# Organ_fix1.net
KiCad netlist of a schematic drawn in EAGLE
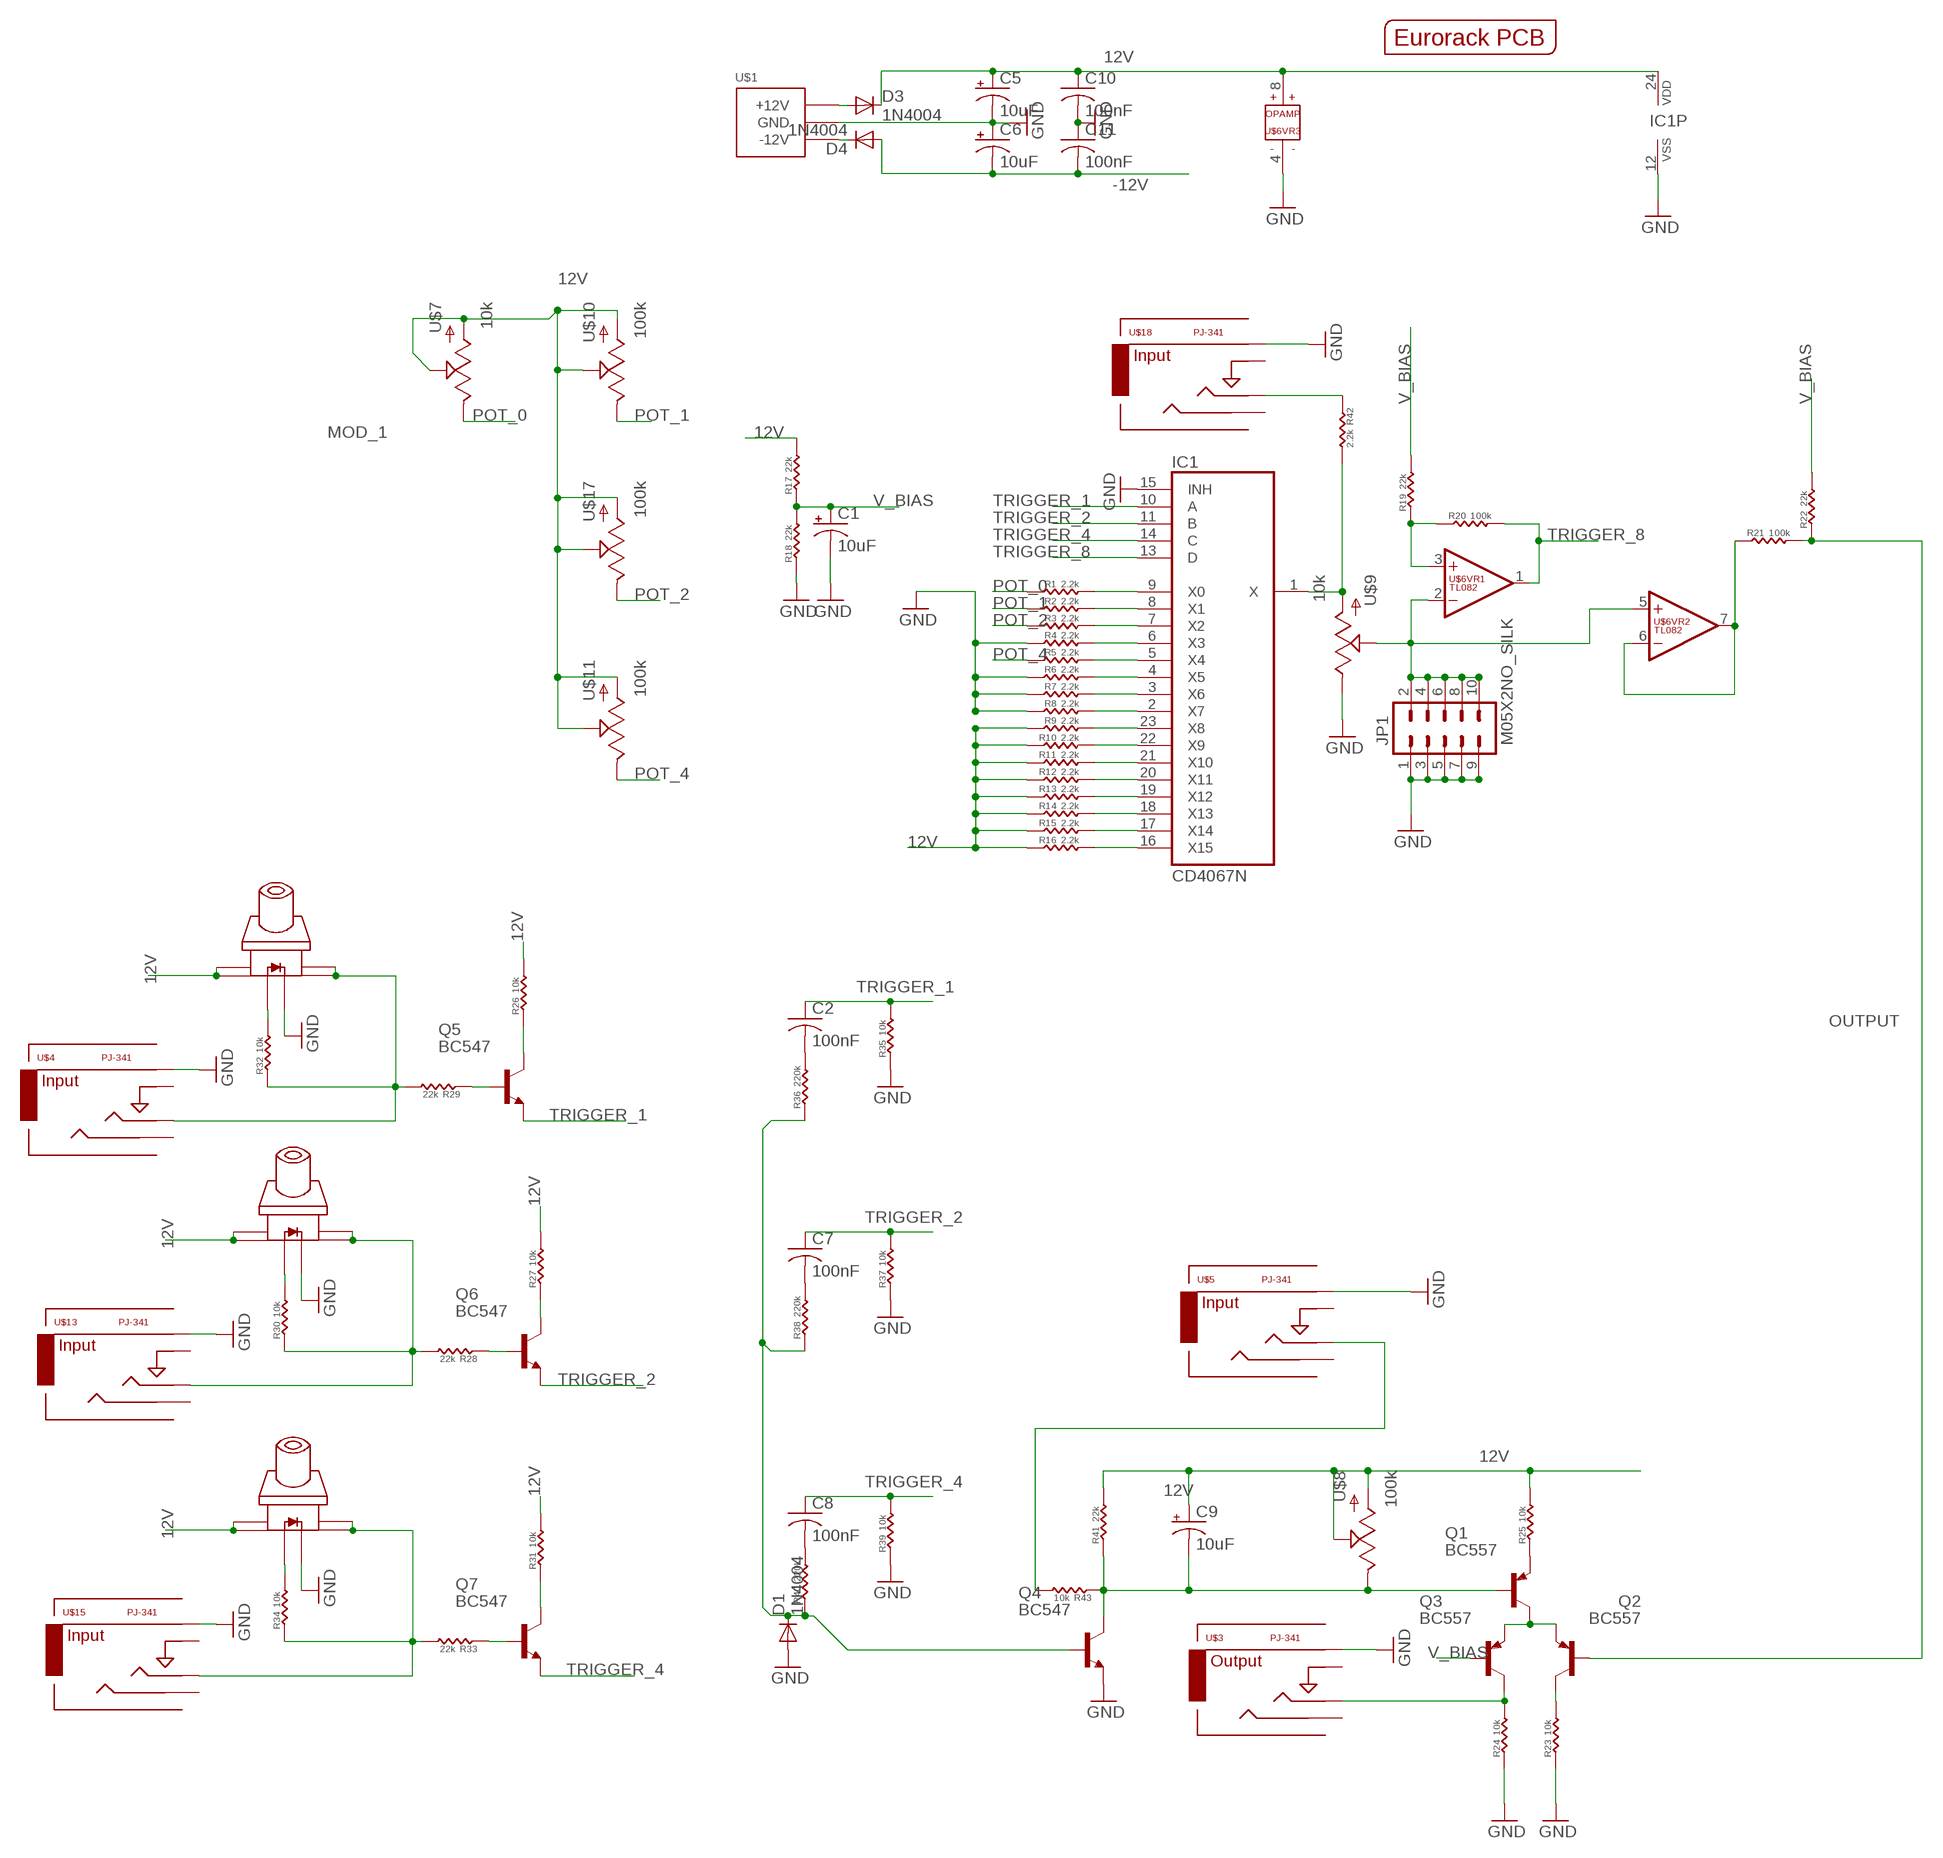
[diagram p0: schematic, sheet 1]

(export (version "E")
  (design (tool "Eeschema 10.0.6"))
  (components
    (comp (ref "C1")
      (value "10uF")
      (footprint "eagle-import:TT2D6")
      (libsource (lib "eagle-import") (part "CPOL-USTT2D6"))
    )
    (comp (ref "C2")
      (value "100nF")
      (footprint "eagle-import:C050-025X075")
      (libsource (lib "eagle-import") (part "C-US050-025X075"))
    )
    (comp (ref "C5")
      (value "10uF")
      (footprint "eagle-import:TT2D6")
      (libsource (lib "eagle-import") (part "CPOL-USTT2D6"))
    )
    (comp (ref "C6")
      (value "10uF")
      (footprint "eagle-import:TT2D6")
      (libsource (lib "eagle-import") (part "CPOL-USTT2D6"))
    )
    (comp (ref "C7")
      (value "100nF")
      (footprint "eagle-import:C050-025X075")
      (libsource (lib "eagle-import") (part "C-US050-025X075"))
    )
    (comp (ref "C8")
      (value "100nF")
      (footprint "eagle-import:C050-025X075")
      (libsource (lib "eagle-import") (part "C-US050-025X075"))
    )
    (comp (ref "C9")
      (value "10uF")
      (footprint "eagle-import:TT2D6")
      (libsource (lib "eagle-import") (part "CPOL-USTT2D6"))
    )
    (comp (ref "C10")
      (value "100nF")
      (footprint "eagle-import:C050-025X075")
      (libsource (lib "eagle-import") (part "C-US050-025X075"))
    )
    (comp (ref "C11")
      (value "100nF")
      (footprint "eagle-import:C050-025X075")
      (libsource (lib "eagle-import") (part "C-US050-025X075"))
    )
    (comp (ref "D1")
      (value "1N4004")
      (footprint "eagle-import:DO41-10")
      (libsource (lib "eagle-import") (part "1N4004"))
    )
    (comp (ref "D3")
      (value "1N4004")
      (footprint "eagle-import:DO41-10")
      (libsource (lib "eagle-import") (part "1N4004"))
    )
    (comp (ref "D4")
      (value "1N4004")
      (footprint "eagle-import:DO41-10")
      (libsource (lib "eagle-import") (part "1N4004"))
    )
    (comp (ref "IC1")
      (value "CD4067N")
      (footprint "eagle-import:DIL24-6")
      (libsource (lib "eagle-import") (part "4067N"))
    )
    (comp (ref "JP1")
      (value "M05X2NO_SILK")
      (footprint "eagle-import:2X5_NOSILK")
      (libsource (lib "eagle-import") (part "M05X2NO_SILK"))
    )
    (comp (ref "Q1")
      (value "BC557")
      (footprint "eagle-import:TO92")
      (libsource (lib "eagle-import") (part "BC557TO92"))
    )
    (comp (ref "Q2")
      (value "BC557")
      (footprint "eagle-import:TO92")
      (libsource (lib "eagle-import") (part "BC557TO92"))
    )
    (comp (ref "Q3")
      (value "BC557")
      (footprint "eagle-import:TO92")
      (libsource (lib "eagle-import") (part "BC557TO92"))
    )
    (comp (ref "Q4")
      (value "BC547")
      (footprint "eagle-import:TO92")
      (libsource (lib "eagle-import") (part "BC547"))
    )
    (comp (ref "Q5")
      (value "BC547")
      (footprint "eagle-import:TO92")
      (libsource (lib "eagle-import") (part "BC547"))
    )
    (comp (ref "Q6")
      (value "BC547")
      (footprint "eagle-import:TO92")
      (libsource (lib "eagle-import") (part "BC547"))
    )
    (comp (ref "Q7")
      (value "BC547")
      (footprint "eagle-import:TO92")
      (libsource (lib "eagle-import") (part "BC547"))
    )
    (comp (ref "R1")
      (value "2.2k")
      (footprint "eagle-import:0204_5")
      (libsource (lib "eagle-import") (part "R-US_0204/5"))
    )
    (comp (ref "R2")
      (value "2.2k")
      (footprint "eagle-import:0204_5")
      (libsource (lib "eagle-import") (part "R-US_0204/5"))
    )
    (comp (ref "R3")
      (value "2.2k")
      (footprint "eagle-import:0204_5")
      (libsource (lib "eagle-import") (part "R-US_0204/5"))
    )
    (comp (ref "R4")
      (value "2.2k")
      (footprint "eagle-import:0204_5")
      (libsource (lib "eagle-import") (part "R-US_0204/5"))
    )
    (comp (ref "R5")
      (value "2.2k")
      (footprint "eagle-import:0204_5")
      (libsource (lib "eagle-import") (part "R-US_0204/5"))
    )
    (comp (ref "R6")
      (value "2.2k")
      (footprint "eagle-import:0204_5")
      (libsource (lib "eagle-import") (part "R-US_0204/5"))
    )
    (comp (ref "R7")
      (value "2.2k")
      (footprint "eagle-import:0204_5")
      (libsource (lib "eagle-import") (part "R-US_0204/5"))
    )
    (comp (ref "R8")
      (value "2.2k")
      (footprint "eagle-import:0204_5")
      (libsource (lib "eagle-import") (part "R-US_0204/5"))
    )
    (comp (ref "R9")
      (value "2.2k")
      (footprint "eagle-import:0204_5")
      (libsource (lib "eagle-import") (part "R-US_0204/5"))
    )
    (comp (ref "R10")
      (value "2.2k")
      (footprint "eagle-import:0204_5")
      (libsource (lib "eagle-import") (part "R-US_0204/5"))
    )
    (comp (ref "R11")
      (value "2.2k")
      (footprint "eagle-import:0204_5")
      (libsource (lib "eagle-import") (part "R-US_0204/5"))
    )
    (comp (ref "R12")
      (value "2.2k")
      (footprint "eagle-import:0204_5")
      (libsource (lib "eagle-import") (part "R-US_0204/5"))
    )
    (comp (ref "R13")
      (value "2.2k")
      (footprint "eagle-import:0204_5")
      (libsource (lib "eagle-import") (part "R-US_0204/5"))
    )
    (comp (ref "R14")
      (value "2.2k")
      (footprint "eagle-import:0204_5")
      (libsource (lib "eagle-import") (part "R-US_0204/5"))
    )
    (comp (ref "R15")
      (value "2.2k")
      (footprint "eagle-import:0204_5")
      (libsource (lib "eagle-import") (part "R-US_0204/5"))
    )
    (comp (ref "R16")
      (value "2.2k")
      (footprint "eagle-import:0204_5")
      (libsource (lib "eagle-import") (part "R-US_0204/5"))
    )
    (comp (ref "R17")
      (value "22k")
      (footprint "eagle-import:0204_5")
      (libsource (lib "eagle-import") (part "R-US_0204/5"))
    )
    (comp (ref "R18")
      (value "22k")
      (footprint "eagle-import:0204_5")
      (libsource (lib "eagle-import") (part "R-US_0204/5"))
    )
    (comp (ref "R19")
      (value "22k")
      (footprint "eagle-import:0204_5")
      (libsource (lib "eagle-import") (part "R-US_0204/5"))
    )
    (comp (ref "R20")
      (value "100k")
      (footprint "eagle-import:0204_5")
      (libsource (lib "eagle-import") (part "R-US_0204/5"))
    )
    (comp (ref "R21")
      (value "100k")
      (footprint "eagle-import:0204_5")
      (libsource (lib "eagle-import") (part "R-US_0204/5"))
    )
    (comp (ref "R22")
      (value "22k")
      (footprint "eagle-import:0204_5")
      (libsource (lib "eagle-import") (part "R-US_0204/5"))
    )
    (comp (ref "R23")
      (value "10k")
      (footprint "eagle-import:0204_5")
      (libsource (lib "eagle-import") (part "R-US_0204/5"))
    )
    (comp (ref "R24")
      (value "10k")
      (footprint "eagle-import:0204_5")
      (libsource (lib "eagle-import") (part "R-US_0204/5"))
    )
    (comp (ref "R25")
      (value "10k")
      (footprint "eagle-import:0204_5")
      (libsource (lib "eagle-import") (part "R-US_0204/5"))
    )
    (comp (ref "R26")
      (value "10k")
      (footprint "eagle-import:0204_5")
      (libsource (lib "eagle-import") (part "R-US_0204/5"))
    )
    (comp (ref "R27")
      (value "10k")
      (footprint "eagle-import:0204_5")
      (libsource (lib "eagle-import") (part "R-US_0204/5"))
    )
    (comp (ref "R28")
      (value "22k")
      (footprint "eagle-import:0204_5")
      (libsource (lib "eagle-import") (part "R-US_0204/5"))
    )
    (comp (ref "R29")
      (value "22k")
      (footprint "eagle-import:0204_5")
      (libsource (lib "eagle-import") (part "R-US_0204/5"))
    )
    (comp (ref "R30")
      (value "10k")
      (footprint "eagle-import:0204_5")
      (libsource (lib "eagle-import") (part "R-US_0204/5"))
    )
    (comp (ref "R31")
      (value "10k")
      (footprint "eagle-import:0204_5")
      (libsource (lib "eagle-import") (part "R-US_0204/5"))
    )
    (comp (ref "R32")
      (value "10k")
      (footprint "eagle-import:0204_5")
      (libsource (lib "eagle-import") (part "R-US_0204/5"))
    )
    (comp (ref "R33")
      (value "22k")
      (footprint "eagle-import:0204_5")
      (libsource (lib "eagle-import") (part "R-US_0204/5"))
    )
    (comp (ref "R34")
      (value "10k")
      (footprint "eagle-import:0204_5")
      (libsource (lib "eagle-import") (part "R-US_0204/5"))
    )
    (comp (ref "R35")
      (value "10k")
      (footprint "eagle-import:0204_5")
      (libsource (lib "eagle-import") (part "R-US_0204/5"))
    )
    (comp (ref "R36")
      (value "220k")
      (footprint "eagle-import:0204_5")
      (libsource (lib "eagle-import") (part "R-US_0204/5"))
    )
    (comp (ref "R37")
      (value "10k")
      (footprint "eagle-import:0204_5")
      (libsource (lib "eagle-import") (part "R-US_0204/5"))
    )
    (comp (ref "R38")
      (value "220k")
      (footprint "eagle-import:0204_5")
      (libsource (lib "eagle-import") (part "R-US_0204/5"))
    )
    (comp (ref "R39")
      (value "10k")
      (footprint "eagle-import:0204_5")
      (libsource (lib "eagle-import") (part "R-US_0204/5"))
    )
    (comp (ref "R40")
      (value "220k")
      (footprint "eagle-import:0204_5")
      (libsource (lib "eagle-import") (part "R-US_0204/5"))
    )
    (comp (ref "R41")
      (value "22k")
      (footprint "eagle-import:0204_5")
      (libsource (lib "eagle-import") (part "R-US_0204/5"))
    )
    (comp (ref "R42")
      (value "2.2k")
      (footprint "eagle-import:0204_5")
      (libsource (lib "eagle-import") (part "R-US_0204/5"))
    )
    (comp (ref "R43")
      (value "10k")
      (footprint "eagle-import:0204_5")
      (libsource (lib "eagle-import") (part "R-US_0204/5"))
    )
    (comp (ref "U$1")
      (value "POWER_SIMPLE10")
      (footprint "eagle-import:POWER_10")
      (libsource (lib "eagle-import") (part "POWER_SIMPLE10"))
    )
    (comp (ref "U$2")
      (value "EURORACK_PCB12HP")
      (footprint "eagle-import:EURORACK12HPPCB")
      (libsource (lib "eagle-import") (part "EURORACK_PCB12HP"))
    )
    (comp (ref "U$3")
      (value "PJ-341")
      (footprint "eagle-import:3.5MM-JACK-SWITCH-13MM-OUTPUT")
      (libsource (lib "eagle-import") (part "AUDIO-JACKOUTPUT"))
    )
    (comp (ref "U$4")
      (value "PJ-341")
      (footprint "eagle-import:3.5MM-JACK-SWITCH-13MM-INPUT")
      (libsource (lib "eagle-import") (part "AUDIO-JACKINPUT"))
    )
    (comp (ref "U$5")
      (value "PJ-341")
      (footprint "eagle-import:3.5MM-JACK-SWITCH-13MM-INPUT")
      (libsource (lib "eagle-import") (part "AUDIO-JACKINPUT"))
    )
    (comp (ref "U$6")
      (value "TL082")
      (footprint "eagle-import:DIL08")
      (libsource (lib "eagle-import") (part "TL072DIP"))
    )
    (comp (ref "U$7")
      (value "10k")
      (footprint "eagle-import:POT_SMALLERHOLE")
      (libsource (lib "eagle-import") (part "POTZEPHPOT_SMALLHOLE"))
    )
    (comp (ref "U$8")
      (value "100k")
      (footprint "eagle-import:POT_SMALLERHOLE")
      (libsource (lib "eagle-import") (part "POTZEPHPOT_SMALLHOLE"))
    )
    (comp (ref "U$9")
      (value "10k")
      (footprint "eagle-import:POT_SMALLERHOLE")
      (libsource (lib "eagle-import") (part "POTZEPHPOT_SMALLHOLE"))
    )
    (comp (ref "U$10")
      (value "100k")
      (footprint "eagle-import:POT_SMALLERHOLE")
      (libsource (lib "eagle-import") (part "POTZEPHPOT_SMALLHOLE"))
    )
    (comp (ref "U$11")
      (value "100k")
      (footprint "eagle-import:POT_SMALLERHOLE")
      (libsource (lib "eagle-import") (part "POTZEPHPOT_SMALLHOLE"))
    )
    (comp (ref "U$12")
      (value "SWITCH_W_LED_PB6149L-X-102YELLOW")
      (footprint "eagle-import:PB6149L")
      (libsource (lib "eagle-import") (part "SWITCH_W_LED_PB6149L-X-102YELLOW"))
    )
    (comp (ref "U$13")
      (value "PJ-341")
      (footprint "eagle-import:3.5MM-JACK-SWITCH-13MM-INPUT")
      (libsource (lib "eagle-import") (part "AUDIO-JACKINPUT"))
    )
    (comp (ref "U$14")
      (value "SWITCH_W_LED_PB6149L-X-102YELLOW")
      (footprint "eagle-import:PB6149L")
      (libsource (lib "eagle-import") (part "SWITCH_W_LED_PB6149L-X-102YELLOW"))
    )
    (comp (ref "U$15")
      (value "PJ-341")
      (footprint "eagle-import:3.5MM-JACK-SWITCH-13MM-INPUT")
      (libsource (lib "eagle-import") (part "AUDIO-JACKINPUT"))
    )
    (comp (ref "U$16")
      (value "SWITCH_W_LED_PB6149L-X-102YELLOW")
      (footprint "eagle-import:PB6149L")
      (libsource (lib "eagle-import") (part "SWITCH_W_LED_PB6149L-X-102YELLOW"))
    )
    (comp (ref "U$17")
      (value "100k")
      (footprint "eagle-import:POT_SMALLERHOLE")
      (libsource (lib "eagle-import") (part "POTZEPHPOT_SMALLHOLE"))
    )
    (comp (ref "U$18")
      (value "PJ-341")
      (footprint "eagle-import:3.5MM-JACK-SWITCH-13MM-INPUT")
      (libsource (lib "eagle-import") (part "AUDIO-JACKINPUT"))
    )
  )
  (nets
    (net (code "1") (name "/-12V") (class "Default")
      (node (ref "C11") (pin "2") (pinfunction "2_2") (pintype "passive"))
      (node (ref "C6") (pin "-") (pinfunction "-_-") (pintype "passive"))
      (node (ref "D4") (pin "A") (pinfunction "A_A") (pintype "passive"))
    )
    (net (code "2") (name "/12V") (class "Default")
      (node (ref "C10") (pin "1") (pinfunction "1_1") (pintype "passive"))
      (node (ref "C5") (pin "+") (pinfunction "+_+") (pintype "passive"))
      (node (ref "C9") (pin "+") (pinfunction "+_+") (pintype "passive"))
      (node (ref "D3") (pin "C") (pinfunction "C_C") (pintype "passive"))
      (node (ref "IC1") (pin "24") (pinfunction "VDD_24") (pintype "power_in"))
      (node (ref "R10") (pin "1") (pinfunction "1_1") (pintype "passive"))
      (node (ref "R11") (pin "1") (pinfunction "1_1") (pintype "passive"))
      (node (ref "R12") (pin "1") (pinfunction "1_1") (pintype "passive"))
      (node (ref "R13") (pin "1") (pinfunction "1_1") (pintype "passive"))
      (node (ref "R14") (pin "1") (pinfunction "1_1") (pintype "passive"))
      (node (ref "R15") (pin "1") (pinfunction "1_1") (pintype "passive"))
      (node (ref "R16") (pin "1") (pinfunction "1_1") (pintype "passive"))
      (node (ref "R17") (pin "2") (pinfunction "2_2") (pintype "passive"))
      (node (ref "R25") (pin "2") (pinfunction "2_2") (pintype "passive"))
      (node (ref "R26") (pin "2") (pinfunction "2_2") (pintype "passive"))
      (node (ref "R27") (pin "2") (pinfunction "2_2") (pintype "passive"))
      (node (ref "R31") (pin "2") (pinfunction "2_2") (pintype "passive"))
      (node (ref "R41") (pin "2") (pinfunction "2_2") (pintype "passive"))
      (node (ref "R9") (pin "1") (pinfunction "1_1") (pintype "passive"))
      (node (ref "U$10") (pin "P$2") (pinfunction "S_P$2") (pintype "passive"))
      (node (ref "U$10") (pin "P$3") (pinfunction "A_P$3") (pintype "passive"))
      (node (ref "U$11") (pin "P$2") (pinfunction "S_P$2") (pintype "passive"))
      (node (ref "U$11") (pin "P$3") (pinfunction "A_P$3") (pintype "passive"))
      (node (ref "U$12") (pin "1") (pinfunction "1_1") (pintype "bidirectional"))
      (node (ref "U$12") (pin "2") (pinfunction "2_2") (pintype "bidirectional"))
      (node (ref "U$14") (pin "1") (pinfunction "1_1") (pintype "bidirectional"))
      (node (ref "U$14") (pin "2") (pinfunction "2_2") (pintype "bidirectional"))
      (node (ref "U$16") (pin "1") (pinfunction "1_1") (pintype "bidirectional"))
      (node (ref "U$16") (pin "2") (pinfunction "2_2") (pintype "bidirectional"))
      (node (ref "U$17") (pin "P$2") (pinfunction "S_P$2") (pintype "passive"))
      (node (ref "U$17") (pin "P$3") (pinfunction "A_P$3") (pintype "passive"))
      (node (ref "U$6") (pin "8") (pinfunction "V+_8") (pintype "power_in"))
      (node (ref "U$7") (pin "P$2") (pinfunction "S_P$2") (pintype "passive"))
      (node (ref "U$7") (pin "P$3") (pinfunction "A_P$3") (pintype "passive"))
      (node (ref "U$8") (pin "P$2") (pinfunction "S_P$2") (pintype "passive"))
      (node (ref "U$8") (pin "P$3") (pinfunction "A_P$3") (pintype "passive"))
    )
    (net (code "3") (name "/MOD_1") (class "Default")
      (node (ref "IC1") (pin "1") (pinfunction "X_1") (pintype "output"))
      (node (ref "R42") (pin "2") (pinfunction "2_2") (pintype "passive"))
      (node (ref "U$9") (pin "P$3") (pinfunction "A_P$3") (pintype "passive"))
    )
    (net (code "4") (name "/OUTPUT") (class "Default")
      (node (ref "Q2") (pin "2") (pinfunction "B_2") (pintype "passive"))
      (node (ref "R21") (pin "2") (pinfunction "2_2") (pintype "passive"))
      (node (ref "R22") (pin "1") (pinfunction "1_1") (pintype "passive"))
    )
    (net (code "5") (name "/POT_0") (class "Default")
      (node (ref "R1") (pin "1") (pinfunction "1_1") (pintype "passive"))
      (node (ref "U$7") (pin "P$1") (pinfunction "E_P$1") (pintype "passive"))
    )
    (net (code "6") (name "/POT_1") (class "Default")
      (node (ref "R2") (pin "1") (pinfunction "1_1") (pintype "passive"))
      (node (ref "U$10") (pin "P$1") (pinfunction "E_P$1") (pintype "passive"))
    )
    (net (code "7") (name "/POT_2") (class "Default")
      (node (ref "R3") (pin "1") (pinfunction "1_1") (pintype "passive"))
      (node (ref "U$17") (pin "P$1") (pinfunction "E_P$1") (pintype "passive"))
    )
    (net (code "8") (name "/POT_4") (class "Default")
      (node (ref "R5") (pin "1") (pinfunction "1_1") (pintype "passive"))
      (node (ref "U$11") (pin "P$1") (pinfunction "E_P$1") (pintype "passive"))
    )
    (net (code "9") (name "/TRIGGER_1") (class "Default")
      (node (ref "C2") (pin "1") (pinfunction "1_1") (pintype "passive"))
      (node (ref "IC1") (pin "10") (pinfunction "A_10") (pintype "input"))
      (node (ref "Q5") (pin "1") (pinfunction "E_1") (pintype "passive"))
      (node (ref "R35") (pin "2") (pinfunction "2_2") (pintype "passive"))
    )
    (net (code "10") (name "/TRIGGER_2") (class "Default")
      (node (ref "C7") (pin "1") (pinfunction "1_1") (pintype "passive"))
      (node (ref "IC1") (pin "11") (pinfunction "B_11") (pintype "input"))
      (node (ref "Q6") (pin "1") (pinfunction "E_1") (pintype "passive"))
      (node (ref "R37") (pin "2") (pinfunction "2_2") (pintype "passive"))
    )
    (net (code "11") (name "/TRIGGER_4") (class "Default")
      (node (ref "C8") (pin "1") (pinfunction "1_1") (pintype "passive"))
      (node (ref "IC1") (pin "14") (pinfunction "C_14") (pintype "input"))
      (node (ref "Q7") (pin "1") (pinfunction "E_1") (pintype "passive"))
      (node (ref "R39") (pin "2") (pinfunction "2_2") (pintype "passive"))
    )
    (net (code "12") (name "/TRIGGER_8") (class "Default")
      (node (ref "IC1") (pin "13") (pinfunction "D_13") (pintype "input"))
      (node (ref "R20") (pin "2") (pinfunction "2_2") (pintype "passive"))
      (node (ref "U$6") (pin "1") (pinfunction "OUT_1") (pintype "output"))
    )
    (net (code "13") (name "/V_BIAS") (class "Default")
      (node (ref "C1") (pin "+") (pinfunction "+_+") (pintype "passive"))
      (node (ref "Q3") (pin "2") (pinfunction "B_2") (pintype "passive"))
      (node (ref "R17") (pin "1") (pinfunction "1_1") (pintype "passive"))
      (node (ref "R18") (pin "2") (pinfunction "2_2") (pintype "passive"))
      (node (ref "R19") (pin "2") (pinfunction "2_2") (pintype "passive"))
      (node (ref "R22") (pin "2") (pinfunction "2_2") (pintype "passive"))
    )
    (net (code "14") (name "GND") (class "Default")
      (node (ref "C1") (pin "-") (pinfunction "-_-") (pintype "passive"))
      (node (ref "C10") (pin "2") (pinfunction "2_2") (pintype "passive"))
      (node (ref "C11") (pin "1") (pinfunction "1_1") (pintype "passive"))
      (node (ref "C5") (pin "-") (pinfunction "-_-") (pintype "passive"))
      (node (ref "C6") (pin "+") (pinfunction "+_+") (pintype "passive"))
      (node (ref "D1") (pin "A") (pinfunction "A_A") (pintype "passive"))
      (node (ref "IC1") (pin "12") (pinfunction "VSS_12") (pintype "power_in"))
      (node (ref "IC1") (pin "15") (pinfunction "INH_15") (pintype "input"))
      (node (ref "JP1") (pin "1") (pinfunction "1_1") (pintype "passive"))
      (node (ref "JP1") (pin "3") (pinfunction "3_3") (pintype "passive"))
      (node (ref "JP1") (pin "5") (pinfunction "5_5") (pintype "passive"))
      (node (ref "JP1") (pin "7") (pinfunction "7_7") (pintype "passive"))
      (node (ref "JP1") (pin "9") (pinfunction "9_9") (pintype "passive"))
      (node (ref "Q4") (pin "1") (pinfunction "E_1") (pintype "passive"))
      (node (ref "R18") (pin "1") (pinfunction "1_1") (pintype "passive"))
      (node (ref "R23") (pin "1") (pinfunction "1_1") (pintype "passive"))
      (node (ref "R24") (pin "1") (pinfunction "1_1") (pintype "passive"))
      (node (ref "R35") (pin "1") (pinfunction "1_1") (pintype "passive"))
      (node (ref "R37") (pin "1") (pinfunction "1_1") (pintype "passive"))
      (node (ref "R39") (pin "1") (pinfunction "1_1") (pintype "passive"))
      (node (ref "R4") (pin "1") (pinfunction "1_1") (pintype "passive"))
      (node (ref "R6") (pin "1") (pinfunction "1_1") (pintype "passive"))
      (node (ref "R7") (pin "1") (pinfunction "1_1") (pintype "passive"))
      (node (ref "R8") (pin "1") (pinfunction "1_1") (pintype "passive"))
      (node (ref "U$1") (pin "3") (pinfunction "GND_3") (pintype "bidirectional"))
      (node (ref "U$1") (pin "4") (pinfunction "GND_4") (pintype "bidirectional"))
      (node (ref "U$1") (pin "5") (pinfunction "GND_5") (pintype "bidirectional"))
      (node (ref "U$1") (pin "6") (pinfunction "GND_6") (pintype "bidirectional"))
      (node (ref "U$1") (pin "7") (pinfunction "GND_7") (pintype "bidirectional"))
      (node (ref "U$1") (pin "8") (pinfunction "GND_8") (pintype "bidirectional"))
      (node (ref "U$12") (pin "LEDNEG") (pinfunction "NEG_LEDNEG") (pintype "bidirectional"))
      (node (ref "U$13") (pin "RING@3") (pinfunction "RING_RING@3") (pintype "bidirectional"))
      (node (ref "U$14") (pin "LEDNEG") (pinfunction "NEG_LEDNEG") (pintype "bidirectional"))
      (node (ref "U$15") (pin "RING@3") (pinfunction "RING_RING@3") (pintype "bidirectional"))
      (node (ref "U$16") (pin "LEDNEG") (pinfunction "NEG_LEDNEG") (pintype "bidirectional"))
      (node (ref "U$18") (pin "RING@3") (pinfunction "RING_RING@3") (pintype "bidirectional"))
      (node (ref "U$3") (pin "RING@3") (pinfunction "RING_RING@3") (pintype "bidirectional"))
      (node (ref "U$4") (pin "RING@3") (pinfunction "RING_RING@3") (pintype "bidirectional"))
      (node (ref "U$5") (pin "RING@3") (pinfunction "RING_RING@3") (pintype "bidirectional"))
      (node (ref "U$6") (pin "4") (pinfunction "V-_4") (pintype "power_in"))
      (node (ref "U$9") (pin "P$1") (pinfunction "E_P$1") (pintype "passive"))
    )
    (net (code "15") (name "Net-(C2-Pad2)") (class "Default")
      (node (ref "C2") (pin "2") (pinfunction "2_2") (pintype "passive"))
      (node (ref "R36") (pin "2") (pinfunction "2_2") (pintype "passive"))
    )
    (net (code "16") (name "Net-(C7-Pad2)") (class "Default")
      (node (ref "C7") (pin "2") (pinfunction "2_2") (pintype "passive"))
      (node (ref "R38") (pin "2") (pinfunction "2_2") (pintype "passive"))
    )
    (net (code "17") (name "Net-(C8-Pad2)") (class "Default")
      (node (ref "C8") (pin "2") (pinfunction "2_2") (pintype "passive"))
      (node (ref "R40") (pin "2") (pinfunction "2_2") (pintype "passive"))
    )
    (net (code "18") (name "Net-(D3-PadA)") (class "Default")
      (node (ref "D3") (pin "A") (pinfunction "A_A") (pintype "passive"))
      (node (ref "U$1") (pin "10") (pinfunction "+12V_10") (pintype "bidirectional"))
      (node (ref "U$1") (pin "9") (pinfunction "+12V_9") (pintype "bidirectional"))
    )
    (net (code "19") (name "Net-(D4-PadC)") (class "Default")
      (node (ref "D4") (pin "C") (pinfunction "C_C") (pintype "passive"))
      (node (ref "U$1") (pin "1") (pinfunction "-12V_1") (pintype "bidirectional"))
      (node (ref "U$1") (pin "2") (pinfunction "-12V_2") (pintype "bidirectional"))
    )
    (net (code "20") (name "Net-(IC1A-X0)") (class "Default")
      (node (ref "IC1") (pin "9") (pinfunction "X0_9") (pintype "input"))
      (node (ref "R1") (pin "2") (pinfunction "2_2") (pintype "passive"))
    )
    (net (code "21") (name "Net-(IC1A-X1)") (class "Default")
      (node (ref "IC1") (pin "8") (pinfunction "X1_8") (pintype "input"))
      (node (ref "R2") (pin "2") (pinfunction "2_2") (pintype "passive"))
    )
    (net (code "22") (name "Net-(IC1A-X2)") (class "Default")
      (node (ref "IC1") (pin "7") (pinfunction "X2_7") (pintype "input"))
      (node (ref "R3") (pin "2") (pinfunction "2_2") (pintype "passive"))
    )
    (net (code "23") (name "Net-(IC1A-X3)") (class "Default")
      (node (ref "IC1") (pin "6") (pinfunction "X3_6") (pintype "input"))
      (node (ref "R4") (pin "2") (pinfunction "2_2") (pintype "passive"))
    )
    (net (code "24") (name "Net-(IC1A-X4)") (class "Default")
      (node (ref "IC1") (pin "5") (pinfunction "X4_5") (pintype "input"))
      (node (ref "R5") (pin "2") (pinfunction "2_2") (pintype "passive"))
    )
    (net (code "25") (name "Net-(IC1A-X5)") (class "Default")
      (node (ref "IC1") (pin "4") (pinfunction "X5_4") (pintype "input"))
      (node (ref "R6") (pin "2") (pinfunction "2_2") (pintype "passive"))
    )
    (net (code "26") (name "Net-(IC1A-X6)") (class "Default")
      (node (ref "IC1") (pin "3") (pinfunction "X6_3") (pintype "input"))
      (node (ref "R7") (pin "2") (pinfunction "2_2") (pintype "passive"))
    )
    (net (code "27") (name "Net-(IC1A-X7)") (class "Default")
      (node (ref "IC1") (pin "2") (pinfunction "X7_2") (pintype "input"))
      (node (ref "R8") (pin "2") (pinfunction "2_2") (pintype "passive"))
    )
    (net (code "28") (name "Net-(IC1A-X8)") (class "Default")
      (node (ref "IC1") (pin "23") (pinfunction "X8_23") (pintype "input"))
      (node (ref "R9") (pin "2") (pinfunction "2_2") (pintype "passive"))
    )
    (net (code "29") (name "Net-(IC1A-X9)") (class "Default")
      (node (ref "IC1") (pin "22") (pinfunction "X9_22") (pintype "input"))
      (node (ref "R10") (pin "2") (pinfunction "2_2") (pintype "passive"))
    )
    (net (code "30") (name "Net-(IC1A-X10)") (class "Default")
      (node (ref "IC1") (pin "21") (pinfunction "X10_21") (pintype "input"))
      (node (ref "R11") (pin "2") (pinfunction "2_2") (pintype "passive"))
    )
    (net (code "31") (name "Net-(IC1A-X11)") (class "Default")
      (node (ref "IC1") (pin "20") (pinfunction "X11_20") (pintype "input"))
      (node (ref "R12") (pin "2") (pinfunction "2_2") (pintype "passive"))
    )
    (net (code "32") (name "Net-(IC1A-X12)") (class "Default")
      (node (ref "IC1") (pin "19") (pinfunction "X12_19") (pintype "input"))
      (node (ref "R13") (pin "2") (pinfunction "2_2") (pintype "passive"))
    )
    (net (code "33") (name "Net-(IC1A-X13)") (class "Default")
      (node (ref "IC1") (pin "18") (pinfunction "X13_18") (pintype "input"))
      (node (ref "R14") (pin "2") (pinfunction "2_2") (pintype "passive"))
    )
    (net (code "34") (name "Net-(IC1A-X14)") (class "Default")
      (node (ref "IC1") (pin "17") (pinfunction "X14_17") (pintype "input"))
      (node (ref "R15") (pin "2") (pinfunction "2_2") (pintype "passive"))
    )
    (net (code "35") (name "Net-(IC1A-X15)") (class "Default")
      (node (ref "IC1") (pin "16") (pinfunction "X15_16") (pintype "input"))
      (node (ref "R16") (pin "2") (pinfunction "2_2") (pintype "passive"))
    )
    (net (code "36") (name "Net-(Q1-B)") (class "Default")
      (node (ref "C9") (pin "-") (pinfunction "-_-") (pintype "passive"))
      (node (ref "Q1") (pin "2") (pinfunction "B_2") (pintype "passive"))
      (node (ref "Q4") (pin "3") (pinfunction "C_3") (pintype "passive"))
      (node (ref "R41") (pin "1") (pinfunction "1_1") (pintype "passive"))
      (node (ref "R43") (pin "1") (pinfunction "1_1") (pintype "passive"))
      (node (ref "U$8") (pin "P$1") (pinfunction "E_P$1") (pintype "passive"))
    )
    (net (code "37") (name "Net-(Q1-C)") (class "Default")
      (node (ref "Q1") (pin "3") (pinfunction "C_3") (pintype "passive"))
      (node (ref "Q2") (pin "1") (pinfunction "E_1") (pintype "passive"))
      (node (ref "Q3") (pin "1") (pinfunction "E_1") (pintype "passive"))
    )
    (net (code "38") (name "Net-(Q1-E)") (class "Default")
      (node (ref "Q1") (pin "1") (pinfunction "E_1") (pintype "passive"))
      (node (ref "R25") (pin "1") (pinfunction "1_1") (pintype "passive"))
    )
    (net (code "39") (name "Net-(Q2-C)") (class "Default")
      (node (ref "Q2") (pin "3") (pinfunction "C_3") (pintype "passive"))
      (node (ref "R23") (pin "2") (pinfunction "2_2") (pintype "passive"))
    )
    (net (code "40") (name "Net-(Q3-C)") (class "Default")
      (node (ref "Q3") (pin "3") (pinfunction "C_3") (pintype "passive"))
      (node (ref "R24") (pin "2") (pinfunction "2_2") (pintype "passive"))
      (node (ref "U$3") (pin "TIP@3") (pinfunction "TIP_TIP@3") (pintype "bidirectional"))
    )
    (net (code "41") (name "Net-(Q4-B)") (class "Default")
      (node (ref "D1") (pin "C") (pinfunction "C_C") (pintype "passive"))
      (node (ref "Q4") (pin "2") (pinfunction "B_2") (pintype "passive"))
      (node (ref "R36") (pin "1") (pinfunction "1_1") (pintype "passive"))
      (node (ref "R38") (pin "1") (pinfunction "1_1") (pintype "passive"))
      (node (ref "R40") (pin "1") (pinfunction "1_1") (pintype "passive"))
    )
    (net (code "42") (name "Net-(Q5-B)") (class "Default")
      (node (ref "Q5") (pin "2") (pinfunction "B_2") (pintype "passive"))
      (node (ref "R29") (pin "1") (pinfunction "1_1") (pintype "passive"))
    )
    (net (code "43") (name "Net-(Q5-C)") (class "Default")
      (node (ref "Q5") (pin "3") (pinfunction "C_3") (pintype "passive"))
      (node (ref "R26") (pin "1") (pinfunction "1_1") (pintype "passive"))
    )
    (net (code "44") (name "Net-(Q6-B)") (class "Default")
      (node (ref "Q6") (pin "2") (pinfunction "B_2") (pintype "passive"))
      (node (ref "R28") (pin "1") (pinfunction "1_1") (pintype "passive"))
    )
    (net (code "45") (name "Net-(Q6-C)") (class "Default")
      (node (ref "Q6") (pin "3") (pinfunction "C_3") (pintype "passive"))
      (node (ref "R27") (pin "1") (pinfunction "1_1") (pintype "passive"))
    )
    (net (code "46") (name "Net-(Q7-B)") (class "Default")
      (node (ref "Q7") (pin "2") (pinfunction "B_2") (pintype "passive"))
      (node (ref "R33") (pin "1") (pinfunction "1_1") (pintype "passive"))
    )
    (net (code "47") (name "Net-(Q7-C)") (class "Default")
      (node (ref "Q7") (pin "3") (pinfunction "C_3") (pintype "passive"))
      (node (ref "R31") (pin "1") (pinfunction "1_1") (pintype "passive"))
    )
    (net (code "48") (name "Net-(U$4-TIP)") (class "Default")
      (node (ref "R29") (pin "2") (pinfunction "2_2") (pintype "passive"))
      (node (ref "R32") (pin "1") (pinfunction "1_1") (pintype "passive"))
      (node (ref "U$12") (pin "3") (pinfunction "3_3") (pintype "bidirectional"))
      (node (ref "U$12") (pin "4") (pinfunction "4_4") (pintype "bidirectional"))
      (node (ref "U$4") (pin "TIP@3") (pinfunction "TIP_TIP@3") (pintype "bidirectional"))
    )
    (net (code "49") (name "Net-(U$5-TIP)") (class "Default")
      (node (ref "R43") (pin "2") (pinfunction "2_2") (pintype "passive"))
      (node (ref "U$5") (pin "TIP@3") (pinfunction "TIP_TIP@3") (pintype "bidirectional"))
    )
    (net (code "50") (name "Net-(U$6A-+IN)") (class "Default")
      (node (ref "R19") (pin "1") (pinfunction "1_1") (pintype "passive"))
      (node (ref "R20") (pin "1") (pinfunction "1_1") (pintype "passive"))
      (node (ref "U$6") (pin "3") (pinfunction "+IN_3") (pintype "input"))
    )
    (net (code "51") (name "Net-(U$6A--IN)") (class "Default")
      (node (ref "JP1") (pin "10") (pinfunction "10_10") (pintype "passive"))
      (node (ref "JP1") (pin "2") (pinfunction "2_2") (pintype "passive"))
      (node (ref "JP1") (pin "4") (pinfunction "4_4") (pintype "passive"))
      (node (ref "JP1") (pin "6") (pinfunction "6_6") (pintype "passive"))
      (node (ref "JP1") (pin "8") (pinfunction "8_8") (pintype "passive"))
      (node (ref "U$6") (pin "2") (pinfunction "-IN_2") (pintype "input"))
      (node (ref "U$6") (pin "5") (pinfunction "+IN_5") (pintype "input"))
      (node (ref "U$9") (pin "P$2") (pinfunction "S_P$2") (pintype "passive"))
    )
    (net (code "52") (name "Net-(U$6B--IN)") (class "Default")
      (node (ref "R21") (pin "1") (pinfunction "1_1") (pintype "passive"))
      (node (ref "U$6") (pin "6") (pinfunction "-IN_6") (pintype "input"))
      (node (ref "U$6") (pin "7") (pinfunction "OUT_7") (pintype "output"))
    )
    (net (code "53") (name "Net-(U$12-POS)") (class "Default")
      (node (ref "R32") (pin "2") (pinfunction "2_2") (pintype "passive"))
      (node (ref "U$12") (pin "LEDPOS") (pinfunction "POS_LEDPOS") (pintype "bidirectional"))
    )
    (net (code "54") (name "Net-(U$13-TIP)") (class "Default")
      (node (ref "R28") (pin "2") (pinfunction "2_2") (pintype "passive"))
      (node (ref "R30") (pin "1") (pinfunction "1_1") (pintype "passive"))
      (node (ref "U$13") (pin "TIP@3") (pinfunction "TIP_TIP@3") (pintype "bidirectional"))
      (node (ref "U$14") (pin "3") (pinfunction "3_3") (pintype "bidirectional"))
      (node (ref "U$14") (pin "4") (pinfunction "4_4") (pintype "bidirectional"))
    )
    (net (code "55") (name "Net-(U$14-POS)") (class "Default")
      (node (ref "R30") (pin "2") (pinfunction "2_2") (pintype "passive"))
      (node (ref "U$14") (pin "LEDPOS") (pinfunction "POS_LEDPOS") (pintype "bidirectional"))
    )
    (net (code "56") (name "Net-(U$15-TIP)") (class "Default")
      (node (ref "R33") (pin "2") (pinfunction "2_2") (pintype "passive"))
      (node (ref "R34") (pin "1") (pinfunction "1_1") (pintype "passive"))
      (node (ref "U$15") (pin "TIP@3") (pinfunction "TIP_TIP@3") (pintype "bidirectional"))
      (node (ref "U$16") (pin "3") (pinfunction "3_3") (pintype "bidirectional"))
      (node (ref "U$16") (pin "4") (pinfunction "4_4") (pintype "bidirectional"))
    )
    (net (code "57") (name "Net-(U$16-POS)") (class "Default")
      (node (ref "R34") (pin "2") (pinfunction "2_2") (pintype "passive"))
      (node (ref "U$16") (pin "LEDPOS") (pinfunction "POS_LEDPOS") (pintype "bidirectional"))
    )
    (net (code "58") (name "Net-(U$18-TIP)") (class "Default")
      (node (ref "R42") (pin "1") (pinfunction "1_1") (pintype "passive"))
      (node (ref "U$18") (pin "TIP@3") (pinfunction "TIP_TIP@3") (pintype "bidirectional"))
    )
    (net (code "59") (name "unconnected-(U$3-SECOND-PadSECOND@3)") (class "Default")
      (node (ref "U$3") (pin "SECOND@3") (pinfunction "SECOND_SECOND@3") (pintype "bidirectional"))
    )
    (net (code "60") (name "unconnected-(U$3-SWITCH-PadSWITCH@3)") (class "Default")
      (node (ref "U$3") (pin "SWITCH@3") (pinfunction "SWITCH_SWITCH@3") (pintype "bidirectional"))
    )
    (net (code "61") (name "unconnected-(U$4-SECOND-PadSECOND@3)") (class "Default")
      (node (ref "U$4") (pin "SECOND@3") (pinfunction "SECOND_SECOND@3") (pintype "bidirectional"))
    )
    (net (code "62") (name "unconnected-(U$4-SWITCH-PadSWITCH@3)") (class "Default")
      (node (ref "U$4") (pin "SWITCH@3") (pinfunction "SWITCH_SWITCH@3") (pintype "bidirectional"))
    )
    (net (code "63") (name "unconnected-(U$5-SECOND-PadSECOND@3)") (class "Default")
      (node (ref "U$5") (pin "SECOND@3") (pinfunction "SECOND_SECOND@3") (pintype "bidirectional"))
    )
    (net (code "64") (name "unconnected-(U$5-SWITCH-PadSWITCH@3)") (class "Default")
      (node (ref "U$5") (pin "SWITCH@3") (pinfunction "SWITCH_SWITCH@3") (pintype "bidirectional"))
    )
    (net (code "65") (name "unconnected-(U$13-SECOND-PadSECOND@3)") (class "Default")
      (node (ref "U$13") (pin "SECOND@3") (pinfunction "SECOND_SECOND@3") (pintype "bidirectional"))
    )
    (net (code "66") (name "unconnected-(U$13-SWITCH-PadSWITCH@3)") (class "Default")
      (node (ref "U$13") (pin "SWITCH@3") (pinfunction "SWITCH_SWITCH@3") (pintype "bidirectional"))
    )
    (net (code "67") (name "unconnected-(U$15-SECOND-PadSECOND@3)") (class "Default")
      (node (ref "U$15") (pin "SECOND@3") (pinfunction "SECOND_SECOND@3") (pintype "bidirectional"))
    )
    (net (code "68") (name "unconnected-(U$15-SWITCH-PadSWITCH@3)") (class "Default")
      (node (ref "U$15") (pin "SWITCH@3") (pinfunction "SWITCH_SWITCH@3") (pintype "bidirectional"))
    )
    (net (code "69") (name "unconnected-(U$18-SECOND-PadSECOND@3)") (class "Default")
      (node (ref "U$18") (pin "SECOND@3") (pinfunction "SECOND_SECOND@3") (pintype "bidirectional"))
    )
    (net (code "70") (name "unconnected-(U$18-SWITCH-PadSWITCH@3)") (class "Default")
      (node (ref "U$18") (pin "SWITCH@3") (pinfunction "SWITCH_SWITCH@3") (pintype "bidirectional"))
    )
  )
)
